# pic_k42.net
KiCad netlist of a schematic drawn in EAGLE
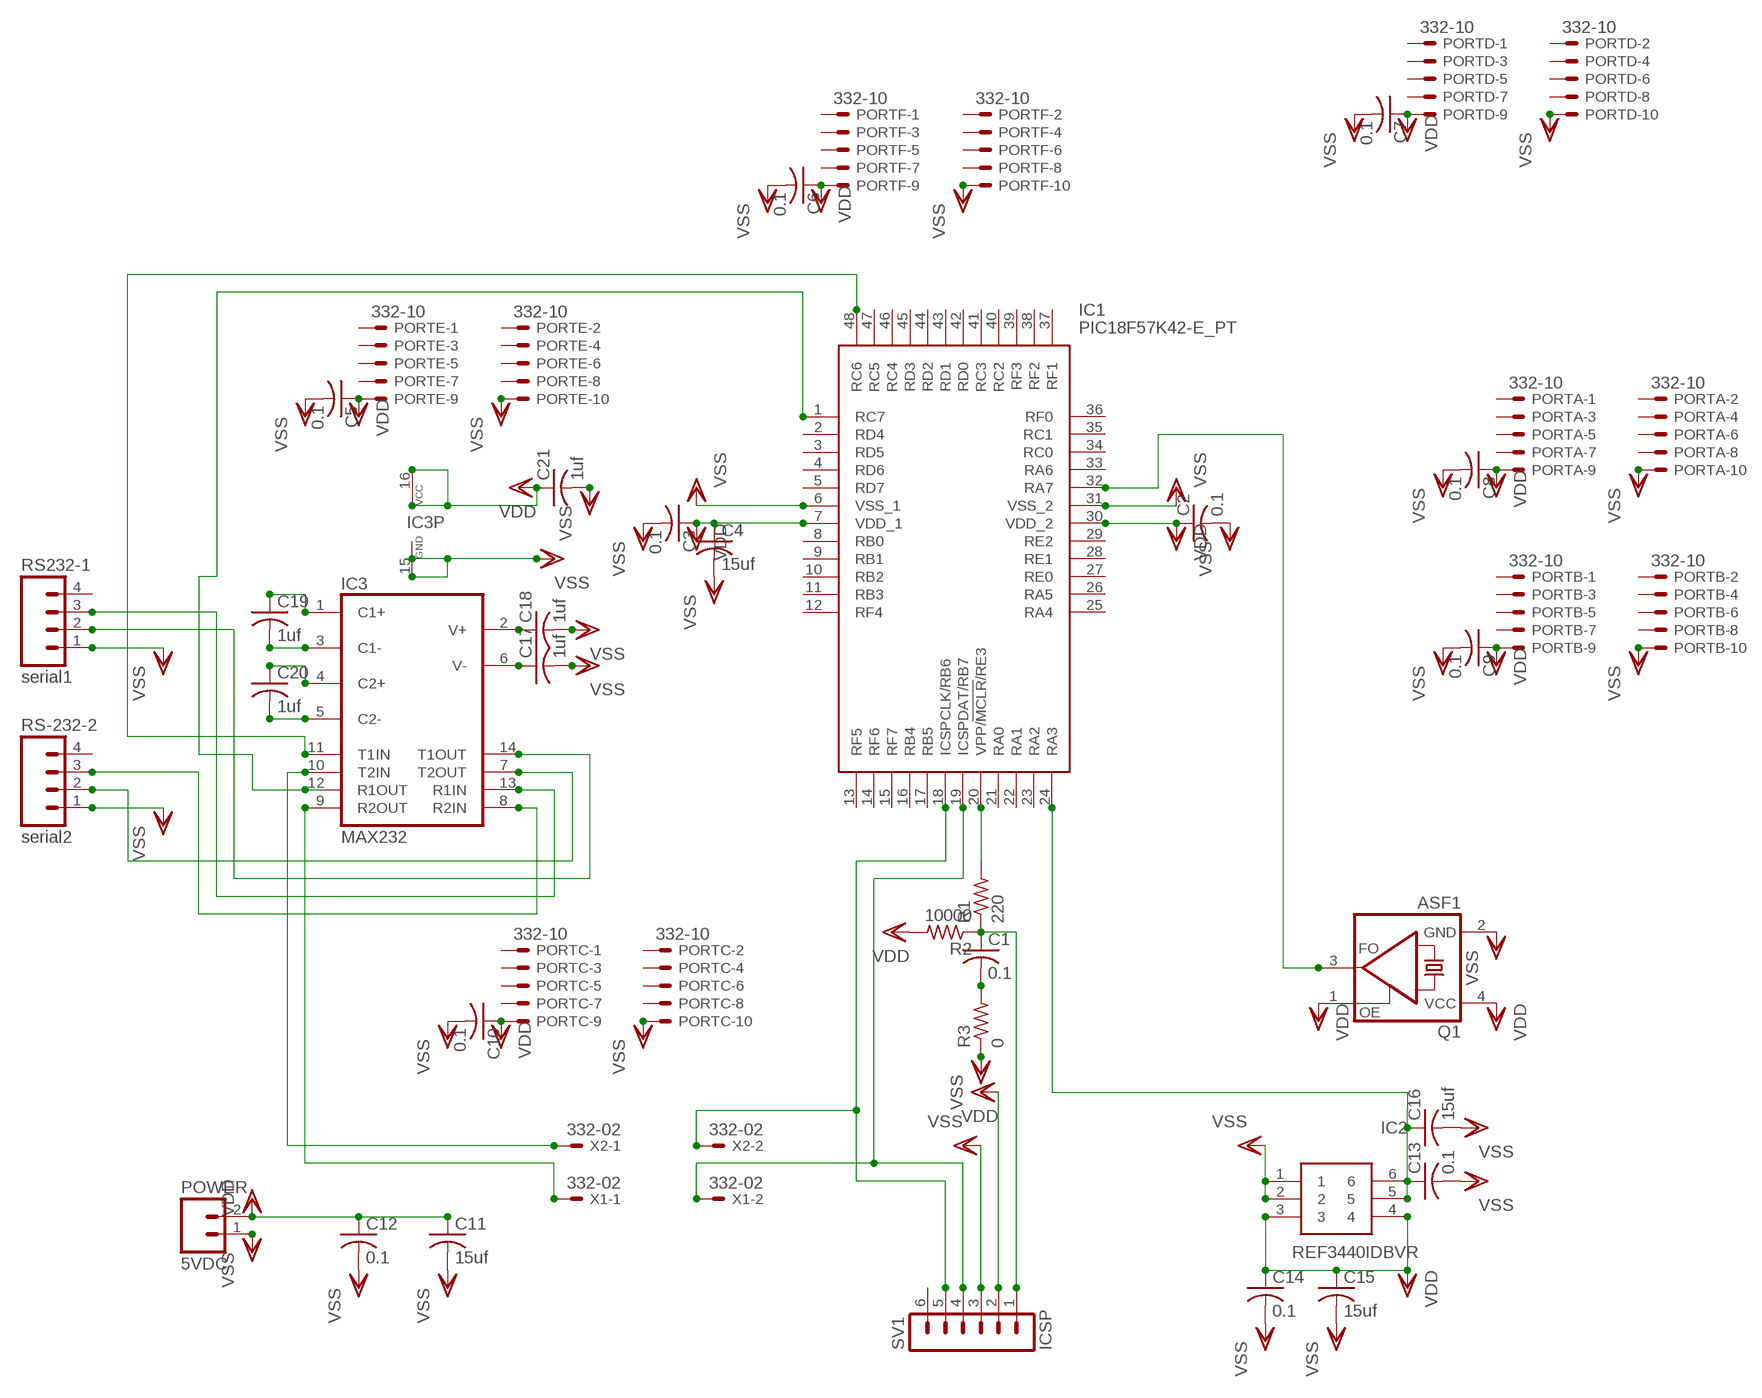
[diagram p0: schematic, sheet 1]

(export (version "E")
  (design (tool "Eeschema 10.0.6"))
  (components
    (comp (ref "C1")
      (value "0.1")
      (footprint "eagle-import:C1206")
      (libsource (lib "eagle-import") (part "C-USC1206"))
    )
    (comp (ref "C2")
      (value "0.1")
      (footprint "eagle-import:C1206")
      (libsource (lib "eagle-import") (part "C-USC1206"))
    )
    (comp (ref "C3")
      (value "0.1")
      (footprint "eagle-import:C1206")
      (libsource (lib "eagle-import") (part "C-USC1206"))
    )
    (comp (ref "C4")
      (value "15uf")
      (footprint "eagle-import:C1206")
      (libsource (lib "eagle-import") (part "C-USC1206"))
    )
    (comp (ref "C5")
      (value "0.1")
      (footprint "eagle-import:C1206")
      (libsource (lib "eagle-import") (part "C-USC1206"))
    )
    (comp (ref "C6")
      (value "0.1")
      (footprint "eagle-import:C1206")
      (libsource (lib "eagle-import") (part "C-USC1206"))
    )
    (comp (ref "C7")
      (value "0.1")
      (footprint "eagle-import:C1206")
      (libsource (lib "eagle-import") (part "C-USC1206"))
    )
    (comp (ref "C8")
      (value "0.1")
      (footprint "eagle-import:C1206")
      (libsource (lib "eagle-import") (part "C-USC1206"))
    )
    (comp (ref "C9")
      (value "0.1")
      (footprint "eagle-import:C1206")
      (libsource (lib "eagle-import") (part "C-USC1206"))
    )
    (comp (ref "C10")
      (value "0.1")
      (footprint "eagle-import:C1206")
      (libsource (lib "eagle-import") (part "C-USC1206"))
    )
    (comp (ref "C11")
      (value "15uf")
      (footprint "eagle-import:C1206")
      (libsource (lib "eagle-import") (part "C-USC1206"))
    )
    (comp (ref "C12")
      (value "0.1")
      (footprint "eagle-import:C1206")
      (libsource (lib "eagle-import") (part "C-USC1206"))
    )
    (comp (ref "C13")
      (value "0.1")
      (footprint "eagle-import:C1206")
      (libsource (lib "eagle-import") (part "C-USC1206"))
    )
    (comp (ref "C14")
      (value "0.1")
      (footprint "eagle-import:C1206")
      (libsource (lib "eagle-import") (part "C-USC1206"))
    )
    (comp (ref "C15")
      (value "15uf")
      (footprint "eagle-import:C1206")
      (libsource (lib "eagle-import") (part "C-USC1206"))
    )
    (comp (ref "C16")
      (value "15uf")
      (footprint "eagle-import:C1206")
      (libsource (lib "eagle-import") (part "C-USC1206"))
    )
    (comp (ref "C17")
      (value "1uf")
      (footprint "eagle-import:C0805")
      (libsource (lib "eagle-import") (part "C-USC0805"))
    )
    (comp (ref "C18")
      (value "1uf")
      (footprint "eagle-import:C0805")
      (libsource (lib "eagle-import") (part "C-USC0805"))
    )
    (comp (ref "C19")
      (value "1uf")
      (footprint "eagle-import:C0805")
      (libsource (lib "eagle-import") (part "C-USC0805"))
    )
    (comp (ref "C20")
      (value "1uf")
      (footprint "eagle-import:C0805")
      (libsource (lib "eagle-import") (part "C-USC0805"))
    )
    (comp (ref "C21")
      (value "1uf")
      (footprint "eagle-import:C0805")
      (libsource (lib "eagle-import") (part "C-USC0805"))
    )
    (comp (ref "IC1")
      (value "PIC18F57K42-E_PT")
      (footprint "eagle-import:QFP50P900X900X120-48N")
      (fields
        (field (name "MANUFACTURER_PART_NUMBER") "PIC18F57K42-E/PT")
        (field (name "MOUSER_PART_NUMBER") "579-PIC18F57K42-E/PT")
      )
      (libsource (lib "eagle-import") (part "PIC18F57K42-E_PT"))
    )
    (comp (ref "IC2")
      (value "REF3440IDBVR")
      (footprint "eagle-import:SOP95P280X145-6N")
      (libsource (lib "eagle-import") (part "REF3440IDBVR"))
    )
    (comp (ref "IC3")
      (value "MAX232")
      (footprint "eagle-import:DIL16")
      (fields (field (name "MF") "MAXIM") (field (name "MPN") "MAX232ACPE+"))
      (libsource (lib "eagle-import") (part "MAX232"))
    )
    (comp (ref "PORTA")
      (value "332-10")
      (footprint "eagle-import:332-10")
      (libsource (lib "eagle-import") (part "332-10"))
    )
    (comp (ref "PORTB")
      (value "332-10")
      (footprint "eagle-import:332-10")
      (libsource (lib "eagle-import") (part "332-10"))
    )
    (comp (ref "PORTC")
      (value "332-10")
      (footprint "eagle-import:332-10")
      (libsource (lib "eagle-import") (part "332-10"))
    )
    (comp (ref "PORTD")
      (value "332-10")
      (footprint "eagle-import:332-10")
      (libsource (lib "eagle-import") (part "332-10"))
    )
    (comp (ref "PORTE")
      (value "332-10")
      (footprint "eagle-import:332-10")
      (libsource (lib "eagle-import") (part "332-10"))
    )
    (comp (ref "PORTF")
      (value "332-10")
      (footprint "eagle-import:332-10")
      (libsource (lib "eagle-import") (part "332-10"))
    )
    (comp (ref "POWER")
      (value "5VDC")
      (footprint "eagle-import:02P")
      (libsource (lib "eagle-import") (part "M02"))
    )
    (comp (ref "Q1")
      (value "ASF1")
      (footprint "eagle-import:ASF")
      (libsource (lib "eagle-import") (part "ASF1"))
    )
    (comp (ref "R1")
      (value "220")
      (footprint "eagle-import:R1206")
      (libsource (lib "eagle-import") (part "R-US_R1206"))
    )
    (comp (ref "R2")
      (value "10000")
      (footprint "eagle-import:R1206")
      (libsource (lib "eagle-import") (part "R-US_R1206"))
    )
    (comp (ref "R3")
      (value "0")
      (footprint "eagle-import:R1206")
      (libsource (lib "eagle-import") (part "R-US_R1206"))
    )
    (comp (ref "RS-232-2")
      (value "serial2")
      (footprint "eagle-import:04P")
      (libsource (lib "eagle-import") (part "M04"))
    )
    (comp (ref "RS232-1")
      (value "serial1")
      (footprint "eagle-import:04P")
      (libsource (lib "eagle-import") (part "M04"))
    )
    (comp (ref "SV1")
      (value "ICSP")
      (footprint "eagle-import:MA06-1")
      (libsource (lib "eagle-import") (part "MA06-1"))
    )
    (comp (ref "X1")
      (value "332-02")
      (footprint "eagle-import:332-02")
      (libsource (lib "eagle-import") (part "332-02"))
    )
    (comp (ref "X2")
      (value "332-02")
      (footprint "eagle-import:332-02")
      (libsource (lib "eagle-import") (part "332-02"))
    )
  )
  (nets
    (net (code "1") (name "Net-(C1-Pad1)") (class "Default")
      (node (ref "C1") (pin "1") (pinfunction "1_1") (pintype "passive"))
      (node (ref "R1") (pin "1") (pinfunction "1_1") (pintype "passive"))
      (node (ref "R2") (pin "1") (pinfunction "1_1") (pintype "passive"))
      (node (ref "SV1") (pin "1") (pinfunction "1_1") (pintype "passive"))
    )
    (net (code "2") (name "Net-(C1-Pad2)") (class "Default")
      (node (ref "C1") (pin "2") (pinfunction "2_2") (pintype "passive"))
      (node (ref "R3") (pin "2") (pinfunction "2_2") (pintype "passive"))
    )
    (net (code "3") (name "Net-(IC1-ICSPCLK{slash}RB6)") (class "Default")
      (node (ref "IC1") (pin "18") (pinfunction "ICSPCLK/RB6_18") (pintype "bidirectional"))
      (node (ref "SV1") (pin "5") (pinfunction "5_5") (pintype "passive"))
      (node (ref "X2") (pin "2") (pinfunction "S_2") (pintype "passive"))
    )
    (net (code "4") (name "Net-(IC1-ICSPDAT{slash}RB7)") (class "Default")
      (node (ref "IC1") (pin "19") (pinfunction "ICSPDAT/RB7_19") (pintype "bidirectional"))
      (node (ref "SV1") (pin "4") (pinfunction "4_4") (pintype "passive"))
      (node (ref "X1") (pin "2") (pinfunction "S_2") (pintype "passive"))
    )
    (net (code "5") (name "Net-(IC1-RA3)") (class "Default")
      (node (ref "C13") (pin "1") (pinfunction "1_1") (pintype "passive"))
      (node (ref "C16") (pin "1") (pinfunction "1_1") (pintype "passive"))
      (node (ref "IC1") (pin "24") (pinfunction "RA3_24") (pintype "bidirectional"))
      (node (ref "IC2") (pin "5") (pinfunction "5_5") (pintype "bidirectional"))
      (node (ref "IC2") (pin "6") (pinfunction "6_6") (pintype "bidirectional"))
    )
    (net (code "6") (name "Net-(IC1-RA7)") (class "Default")
      (node (ref "IC1") (pin "32") (pinfunction "RA7_32") (pintype "bidirectional"))
      (node (ref "Q1") (pin "3") (pinfunction "FO_3") (pintype "output"))
    )
    (net (code "7") (name "Net-(IC1-RC6)") (class "Default")
      (node (ref "IC1") (pin "48") (pinfunction "RC6_48") (pintype "bidirectional"))
      (node (ref "IC3") (pin "11") (pinfunction "T1IN_11") (pintype "input"))
    )
    (net (code "8") (name "Net-(IC1-RC7)") (class "Default")
      (node (ref "IC1") (pin "1") (pinfunction "RC7_1") (pintype "bidirectional"))
      (node (ref "IC3") (pin "12") (pinfunction "R1OUT_12") (pintype "output"))
    )
    (net (code "9") (name "Net-(IC1-VPP{slash}~{MCLR}{slash}RE3)") (class "Default")
      (node (ref "IC1") (pin "20") (pinfunction "VPP/~{MCLR}/RE3_20") (pintype "bidirectional"))
      (node (ref "R1") (pin "2") (pinfunction "2_2") (pintype "passive"))
    )
    (net (code "10") (name "Net-(IC3A-C1+)") (class "Default")
      (node (ref "C19") (pin "1") (pinfunction "1_1") (pintype "passive"))
      (node (ref "IC3") (pin "1") (pinfunction "C1+_1") (pintype "bidirectional"))
    )
    (net (code "11") (name "Net-(IC3A-C1-)") (class "Default")
      (node (ref "C19") (pin "2") (pinfunction "2_2") (pintype "passive"))
      (node (ref "IC3") (pin "3") (pinfunction "C1-_3") (pintype "bidirectional"))
    )
    (net (code "12") (name "Net-(IC3A-C2+)") (class "Default")
      (node (ref "C20") (pin "1") (pinfunction "1_1") (pintype "passive"))
      (node (ref "IC3") (pin "4") (pinfunction "C2+_4") (pintype "bidirectional"))
    )
    (net (code "13") (name "Net-(IC3A-C2-)") (class "Default")
      (node (ref "C20") (pin "2") (pinfunction "2_2") (pintype "passive"))
      (node (ref "IC3") (pin "5") (pinfunction "C2-_5") (pintype "bidirectional"))
    )
    (net (code "14") (name "Net-(IC3A-R1IN)") (class "Default")
      (node (ref "IC3") (pin "13") (pinfunction "R1IN_13") (pintype "input"))
      (node (ref "RS232-1") (pin "3") (pinfunction "3_3") (pintype "passive"))
    )
    (net (code "15") (name "Net-(IC3A-R2IN)") (class "Default")
      (node (ref "IC3") (pin "8") (pinfunction "R2IN_8") (pintype "input"))
      (node (ref "RS-232-2") (pin "3") (pinfunction "3_3") (pintype "passive"))
    )
    (net (code "16") (name "Net-(IC3A-R2OUT)") (class "Default")
      (node (ref "IC3") (pin "9") (pinfunction "R2OUT_9") (pintype "output"))
      (node (ref "X1") (pin "1") (pinfunction "S_1") (pintype "passive"))
    )
    (net (code "17") (name "Net-(IC3A-T1OUT)") (class "Default")
      (node (ref "IC3") (pin "14") (pinfunction "T1OUT_14") (pintype "output"))
      (node (ref "RS232-1") (pin "2") (pinfunction "2_2") (pintype "passive"))
    )
    (net (code "18") (name "Net-(IC3A-T2IN)") (class "Default")
      (node (ref "IC3") (pin "10") (pinfunction "T2IN_10") (pintype "input"))
      (node (ref "X2") (pin "1") (pinfunction "S_1") (pintype "passive"))
    )
    (net (code "19") (name "Net-(IC3A-T2OUT)") (class "Default")
      (node (ref "IC3") (pin "7") (pinfunction "T2OUT_7") (pintype "output"))
      (node (ref "RS-232-2") (pin "2") (pinfunction "2_2") (pintype "passive"))
    )
    (net (code "20") (name "Net-(IC3A-V+)") (class "Default")
      (node (ref "C18") (pin "1") (pinfunction "1_1") (pintype "passive"))
      (node (ref "IC3") (pin "2") (pinfunction "V+_2") (pintype "bidirectional"))
    )
    (net (code "21") (name "Net-(IC3A-V-)") (class "Default")
      (node (ref "C17") (pin "1") (pinfunction "1_1") (pintype "passive"))
      (node (ref "IC3") (pin "6") (pinfunction "V-_6") (pintype "bidirectional"))
    )
    (net (code "22") (name "VDD") (class "Default")
      (node (ref "C10") (pin "1") (pinfunction "1_1") (pintype "passive"))
      (node (ref "C11") (pin "1") (pinfunction "1_1") (pintype "passive"))
      (node (ref "C12") (pin "1") (pinfunction "1_1") (pintype "passive"))
      (node (ref "C14") (pin "1") (pinfunction "1_1") (pintype "passive"))
      (node (ref "C15") (pin "1") (pinfunction "1_1") (pintype "passive"))
      (node (ref "C2") (pin "1") (pinfunction "1_1") (pintype "passive"))
      (node (ref "C21") (pin "1") (pinfunction "1_1") (pintype "passive"))
      (node (ref "C3") (pin "1") (pinfunction "1_1") (pintype "passive"))
      (node (ref "C4") (pin "1") (pinfunction "1_1") (pintype "passive"))
      (node (ref "C5") (pin "1") (pinfunction "1_1") (pintype "passive"))
      (node (ref "C6") (pin "1") (pinfunction "1_1") (pintype "passive"))
      (node (ref "C7") (pin "1") (pinfunction "1_1") (pintype "passive"))
      (node (ref "C8") (pin "1") (pinfunction "1_1") (pintype "passive"))
      (node (ref "C9") (pin "1") (pinfunction "1_1") (pintype "passive"))
      (node (ref "IC1") (pin "30") (pinfunction "VDD_2_30") (pintype "bidirectional"))
      (node (ref "IC1") (pin "7") (pinfunction "VDD_1_7") (pintype "bidirectional"))
      (node (ref "IC2") (pin "3") (pinfunction "3_3") (pintype "bidirectional"))
      (node (ref "IC2") (pin "4") (pinfunction "4_4") (pintype "bidirectional"))
      (node (ref "IC3") (pin "16") (pinfunction "VCC_16") (pintype "power_in"))
      (node (ref "PORTA") (pin "9") (pinfunction "S_9") (pintype "passive"))
      (node (ref "PORTB") (pin "9") (pinfunction "S_9") (pintype "passive"))
      (node (ref "PORTC") (pin "9") (pinfunction "S_9") (pintype "passive"))
      (node (ref "PORTD") (pin "9") (pinfunction "S_9") (pintype "passive"))
      (node (ref "PORTE") (pin "9") (pinfunction "S_9") (pintype "passive"))
      (node (ref "PORTF") (pin "9") (pinfunction "S_9") (pintype "passive"))
      (node (ref "POWER") (pin "2") (pinfunction "2_2") (pintype "passive"))
      (node (ref "Q1") (pin "1") (pinfunction "OE_1") (pintype "input"))
      (node (ref "Q1") (pin "4") (pinfunction "VCC_4") (pintype "power_in"))
      (node (ref "R2") (pin "2") (pinfunction "2_2") (pintype "passive"))
      (node (ref "SV1") (pin "2") (pinfunction "2_2") (pintype "passive"))
    )
    (net (code "23") (name "VSS") (class "Default")
      (node (ref "C10") (pin "2") (pinfunction "2_2") (pintype "passive"))
      (node (ref "C11") (pin "2") (pinfunction "2_2") (pintype "passive"))
      (node (ref "C12") (pin "2") (pinfunction "2_2") (pintype "passive"))
      (node (ref "C13") (pin "2") (pinfunction "2_2") (pintype "passive"))
      (node (ref "C14") (pin "2") (pinfunction "2_2") (pintype "passive"))
      (node (ref "C15") (pin "2") (pinfunction "2_2") (pintype "passive"))
      (node (ref "C16") (pin "2") (pinfunction "2_2") (pintype "passive"))
      (node (ref "C17") (pin "2") (pinfunction "2_2") (pintype "passive"))
      (node (ref "C18") (pin "2") (pinfunction "2_2") (pintype "passive"))
      (node (ref "C2") (pin "2") (pinfunction "2_2") (pintype "passive"))
      (node (ref "C21") (pin "2") (pinfunction "2_2") (pintype "passive"))
      (node (ref "C3") (pin "2") (pinfunction "2_2") (pintype "passive"))
      (node (ref "C4") (pin "2") (pinfunction "2_2") (pintype "passive"))
      (node (ref "C5") (pin "2") (pinfunction "2_2") (pintype "passive"))
      (node (ref "C6") (pin "2") (pinfunction "2_2") (pintype "passive"))
      (node (ref "C7") (pin "2") (pinfunction "2_2") (pintype "passive"))
      (node (ref "C8") (pin "2") (pinfunction "2_2") (pintype "passive"))
      (node (ref "C9") (pin "2") (pinfunction "2_2") (pintype "passive"))
      (node (ref "IC1") (pin "31") (pinfunction "VSS_2_31") (pintype "bidirectional"))
      (node (ref "IC1") (pin "6") (pinfunction "VSS_1_6") (pintype "bidirectional"))
      (node (ref "IC2") (pin "1") (pinfunction "1_1") (pintype "bidirectional"))
      (node (ref "IC2") (pin "2") (pinfunction "2_2") (pintype "bidirectional"))
      (node (ref "IC3") (pin "15") (pinfunction "GND_15") (pintype "power_in"))
      (node (ref "PORTA") (pin "10") (pinfunction "S_10") (pintype "passive"))
      (node (ref "PORTB") (pin "10") (pinfunction "S_10") (pintype "passive"))
      (node (ref "PORTC") (pin "10") (pinfunction "S_10") (pintype "passive"))
      (node (ref "PORTD") (pin "10") (pinfunction "S_10") (pintype "passive"))
      (node (ref "PORTE") (pin "10") (pinfunction "S_10") (pintype "passive"))
      (node (ref "PORTF") (pin "10") (pinfunction "S_10") (pintype "passive"))
      (node (ref "POWER") (pin "1") (pinfunction "1_1") (pintype "passive"))
      (node (ref "Q1") (pin "2") (pinfunction "GND_2") (pintype "power_in"))
      (node (ref "R3") (pin "1") (pinfunction "1_1") (pintype "passive"))
      (node (ref "RS-232-2") (pin "1") (pinfunction "1_1") (pintype "passive"))
      (node (ref "RS232-1") (pin "1") (pinfunction "1_1") (pintype "passive"))
      (node (ref "SV1") (pin "3") (pinfunction "3_3") (pintype "passive"))
    )
    (net (code "24") (name "unconnected-(IC1-RA0-Pad21)") (class "Default")
      (node (ref "IC1") (pin "21") (pinfunction "RA0_21") (pintype "bidirectional"))
    )
    (net (code "25") (name "unconnected-(IC1-RA1-Pad22)") (class "Default")
      (node (ref "IC1") (pin "22") (pinfunction "RA1_22") (pintype "bidirectional"))
    )
    (net (code "26") (name "unconnected-(IC1-RA2-Pad23)") (class "Default")
      (node (ref "IC1") (pin "23") (pinfunction "RA2_23") (pintype "bidirectional"))
    )
    (net (code "27") (name "unconnected-(IC1-RA4-Pad25)") (class "Default")
      (node (ref "IC1") (pin "25") (pinfunction "RA4_25") (pintype "bidirectional"))
    )
    (net (code "28") (name "unconnected-(IC1-RA5-Pad26)") (class "Default")
      (node (ref "IC1") (pin "26") (pinfunction "RA5_26") (pintype "bidirectional"))
    )
    (net (code "29") (name "unconnected-(IC1-RA6-Pad33)") (class "Default")
      (node (ref "IC1") (pin "33") (pinfunction "RA6_33") (pintype "bidirectional"))
    )
    (net (code "30") (name "unconnected-(IC1-RB0-Pad8)") (class "Default")
      (node (ref "IC1") (pin "8") (pinfunction "RB0_8") (pintype "bidirectional"))
    )
    (net (code "31") (name "unconnected-(IC1-RB1-Pad9)") (class "Default")
      (node (ref "IC1") (pin "9") (pinfunction "RB1_9") (pintype "bidirectional"))
    )
    (net (code "32") (name "unconnected-(IC1-RB2-Pad10)") (class "Default")
      (node (ref "IC1") (pin "10") (pinfunction "RB2_10") (pintype "bidirectional"))
    )
    (net (code "33") (name "unconnected-(IC1-RB3-Pad11)") (class "Default")
      (node (ref "IC1") (pin "11") (pinfunction "RB3_11") (pintype "bidirectional"))
    )
    (net (code "34") (name "unconnected-(IC1-RB4-Pad16)") (class "Default")
      (node (ref "IC1") (pin "16") (pinfunction "RB4_16") (pintype "bidirectional"))
    )
    (net (code "35") (name "unconnected-(IC1-RB5-Pad17)") (class "Default")
      (node (ref "IC1") (pin "17") (pinfunction "RB5_17") (pintype "bidirectional"))
    )
    (net (code "36") (name "unconnected-(IC1-RC0-Pad34)") (class "Default")
      (node (ref "IC1") (pin "34") (pinfunction "RC0_34") (pintype "bidirectional"))
    )
    (net (code "37") (name "unconnected-(IC1-RC1-Pad35)") (class "Default")
      (node (ref "IC1") (pin "35") (pinfunction "RC1_35") (pintype "bidirectional"))
    )
    (net (code "38") (name "unconnected-(IC1-RC2-Pad40)") (class "Default")
      (node (ref "IC1") (pin "40") (pinfunction "RC2_40") (pintype "bidirectional"))
    )
    (net (code "39") (name "unconnected-(IC1-RC3-Pad41)") (class "Default")
      (node (ref "IC1") (pin "41") (pinfunction "RC3_41") (pintype "bidirectional"))
    )
    (net (code "40") (name "unconnected-(IC1-RC4-Pad46)") (class "Default")
      (node (ref "IC1") (pin "46") (pinfunction "RC4_46") (pintype "bidirectional"))
    )
    (net (code "41") (name "unconnected-(IC1-RC5-Pad47)") (class "Default")
      (node (ref "IC1") (pin "47") (pinfunction "RC5_47") (pintype "bidirectional"))
    )
    (net (code "42") (name "unconnected-(IC1-RD0-Pad42)") (class "Default")
      (node (ref "IC1") (pin "42") (pinfunction "RD0_42") (pintype "bidirectional"))
    )
    (net (code "43") (name "unconnected-(IC1-RD1-Pad43)") (class "Default")
      (node (ref "IC1") (pin "43") (pinfunction "RD1_43") (pintype "bidirectional"))
    )
    (net (code "44") (name "unconnected-(IC1-RD2-Pad44)") (class "Default")
      (node (ref "IC1") (pin "44") (pinfunction "RD2_44") (pintype "bidirectional"))
    )
    (net (code "45") (name "unconnected-(IC1-RD3-Pad45)") (class "Default")
      (node (ref "IC1") (pin "45") (pinfunction "RD3_45") (pintype "bidirectional"))
    )
    (net (code "46") (name "unconnected-(IC1-RD4-Pad2)") (class "Default")
      (node (ref "IC1") (pin "2") (pinfunction "RD4_2") (pintype "bidirectional"))
    )
    (net (code "47") (name "unconnected-(IC1-RD5-Pad3)") (class "Default")
      (node (ref "IC1") (pin "3") (pinfunction "RD5_3") (pintype "bidirectional"))
    )
    (net (code "48") (name "unconnected-(IC1-RD6-Pad4)") (class "Default")
      (node (ref "IC1") (pin "4") (pinfunction "RD6_4") (pintype "bidirectional"))
    )
    (net (code "49") (name "unconnected-(IC1-RD7-Pad5)") (class "Default")
      (node (ref "IC1") (pin "5") (pinfunction "RD7_5") (pintype "bidirectional"))
    )
    (net (code "50") (name "unconnected-(IC1-RE0-Pad27)") (class "Default")
      (node (ref "IC1") (pin "27") (pinfunction "RE0_27") (pintype "bidirectional"))
    )
    (net (code "51") (name "unconnected-(IC1-RE1-Pad28)") (class "Default")
      (node (ref "IC1") (pin "28") (pinfunction "RE1_28") (pintype "bidirectional"))
    )
    (net (code "52") (name "unconnected-(IC1-RE2-Pad29)") (class "Default")
      (node (ref "IC1") (pin "29") (pinfunction "RE2_29") (pintype "bidirectional"))
    )
    (net (code "53") (name "unconnected-(IC1-RF0-Pad36)") (class "Default")
      (node (ref "IC1") (pin "36") (pinfunction "RF0_36") (pintype "bidirectional"))
    )
    (net (code "54") (name "unconnected-(IC1-RF1-Pad37)") (class "Default")
      (node (ref "IC1") (pin "37") (pinfunction "RF1_37") (pintype "bidirectional"))
    )
    (net (code "55") (name "unconnected-(IC1-RF2-Pad38)") (class "Default")
      (node (ref "IC1") (pin "38") (pinfunction "RF2_38") (pintype "bidirectional"))
    )
    (net (code "56") (name "unconnected-(IC1-RF3-Pad39)") (class "Default")
      (node (ref "IC1") (pin "39") (pinfunction "RF3_39") (pintype "bidirectional"))
    )
    (net (code "57") (name "unconnected-(IC1-RF4-Pad12)") (class "Default")
      (node (ref "IC1") (pin "12") (pinfunction "RF4_12") (pintype "bidirectional"))
    )
    (net (code "58") (name "unconnected-(IC1-RF5-Pad13)") (class "Default")
      (node (ref "IC1") (pin "13") (pinfunction "RF5_13") (pintype "bidirectional"))
    )
    (net (code "59") (name "unconnected-(IC1-RF6-Pad14)") (class "Default")
      (node (ref "IC1") (pin "14") (pinfunction "RF6_14") (pintype "bidirectional"))
    )
    (net (code "60") (name "unconnected-(IC1-RF7-Pad15)") (class "Default")
      (node (ref "IC1") (pin "15") (pinfunction "RF7_15") (pintype "bidirectional"))
    )
    (net (code "61") (name "unconnected-(PORTAA-S-Pad1)") (class "Default")
      (node (ref "PORTA") (pin "1") (pinfunction "S_1") (pintype "passive"))
    )
    (net (code "62") (name "unconnected-(PORTAC-S-Pad2)") (class "Default")
      (node (ref "PORTA") (pin "2") (pinfunction "S_2") (pintype "passive"))
    )
    (net (code "63") (name "unconnected-(PORTAD-S-Pad3)") (class "Default")
      (node (ref "PORTA") (pin "3") (pinfunction "S_3") (pintype "passive"))
    )
    (net (code "64") (name "unconnected-(PORTAE-S-Pad4)") (class "Default")
      (node (ref "PORTA") (pin "4") (pinfunction "S_4") (pintype "passive"))
    )
    (net (code "65") (name "unconnected-(PORTAF-S-Pad5)") (class "Default")
      (node (ref "PORTA") (pin "5") (pinfunction "S_5") (pintype "passive"))
    )
    (net (code "66") (name "unconnected-(PORTAG-S-Pad6)") (class "Default")
      (node (ref "PORTA") (pin "6") (pinfunction "S_6") (pintype "passive"))
    )
    (net (code "67") (name "unconnected-(PORTAH-S-Pad7)") (class "Default")
      (node (ref "PORTA") (pin "7") (pinfunction "S_7") (pintype "passive"))
    )
    (net (code "68") (name "unconnected-(PORTAI-S-Pad8)") (class "Default")
      (node (ref "PORTA") (pin "8") (pinfunction "S_8") (pintype "passive"))
    )
    (net (code "69") (name "unconnected-(PORTBA-S-Pad1)") (class "Default")
      (node (ref "PORTB") (pin "1") (pinfunction "S_1") (pintype "passive"))
    )
    (net (code "70") (name "unconnected-(PORTBC-S-Pad2)") (class "Default")
      (node (ref "PORTB") (pin "2") (pinfunction "S_2") (pintype "passive"))
    )
    (net (code "71") (name "unconnected-(PORTBD-S-Pad3)") (class "Default")
      (node (ref "PORTB") (pin "3") (pinfunction "S_3") (pintype "passive"))
    )
    (net (code "72") (name "unconnected-(PORTBE-S-Pad4)") (class "Default")
      (node (ref "PORTB") (pin "4") (pinfunction "S_4") (pintype "passive"))
    )
    (net (code "73") (name "unconnected-(PORTBF-S-Pad5)") (class "Default")
      (node (ref "PORTB") (pin "5") (pinfunction "S_5") (pintype "passive"))
    )
    (net (code "74") (name "unconnected-(PORTBG-S-Pad6)") (class "Default")
      (node (ref "PORTB") (pin "6") (pinfunction "S_6") (pintype "passive"))
    )
    (net (code "75") (name "unconnected-(PORTBH-S-Pad7)") (class "Default")
      (node (ref "PORTB") (pin "7") (pinfunction "S_7") (pintype "passive"))
    )
    (net (code "76") (name "unconnected-(PORTBI-S-Pad8)") (class "Default")
      (node (ref "PORTB") (pin "8") (pinfunction "S_8") (pintype "passive"))
    )
    (net (code "77") (name "unconnected-(PORTCA-S-Pad1)") (class "Default")
      (node (ref "PORTC") (pin "1") (pinfunction "S_1") (pintype "passive"))
    )
    (net (code "78") (name "unconnected-(PORTCC-S-Pad2)") (class "Default")
      (node (ref "PORTC") (pin "2") (pinfunction "S_2") (pintype "passive"))
    )
    (net (code "79") (name "unconnected-(PORTCD-S-Pad3)") (class "Default")
      (node (ref "PORTC") (pin "3") (pinfunction "S_3") (pintype "passive"))
    )
    (net (code "80") (name "unconnected-(PORTCE-S-Pad4)") (class "Default")
      (node (ref "PORTC") (pin "4") (pinfunction "S_4") (pintype "passive"))
    )
    (net (code "81") (name "unconnected-(PORTCF-S-Pad5)") (class "Default")
      (node (ref "PORTC") (pin "5") (pinfunction "S_5") (pintype "passive"))
    )
    (net (code "82") (name "unconnected-(PORTCG-S-Pad6)") (class "Default")
      (node (ref "PORTC") (pin "6") (pinfunction "S_6") (pintype "passive"))
    )
    (net (code "83") (name "unconnected-(PORTCH-S-Pad7)") (class "Default")
      (node (ref "PORTC") (pin "7") (pinfunction "S_7") (pintype "passive"))
    )
    (net (code "84") (name "unconnected-(PORTCI-S-Pad8)") (class "Default")
      (node (ref "PORTC") (pin "8") (pinfunction "S_8") (pintype "passive"))
    )
    (net (code "85") (name "unconnected-(PORTDA-S-Pad1)") (class "Default")
      (node (ref "PORTD") (pin "1") (pinfunction "S_1") (pintype "passive"))
    )
    (net (code "86") (name "unconnected-(PORTDC-S-Pad2)") (class "Default")
      (node (ref "PORTD") (pin "2") (pinfunction "S_2") (pintype "passive"))
    )
    (net (code "87") (name "unconnected-(PORTDD-S-Pad3)") (class "Default")
      (node (ref "PORTD") (pin "3") (pinfunction "S_3") (pintype "passive"))
    )
    (net (code "88") (name "unconnected-(PORTDE-S-Pad4)") (class "Default")
      (node (ref "PORTD") (pin "4") (pinfunction "S_4") (pintype "passive"))
    )
    (net (code "89") (name "unconnected-(PORTDF-S-Pad5)") (class "Default")
      (node (ref "PORTD") (pin "5") (pinfunction "S_5") (pintype "passive"))
    )
    (net (code "90") (name "unconnected-(PORTDG-S-Pad6)") (class "Default")
      (node (ref "PORTD") (pin "6") (pinfunction "S_6") (pintype "passive"))
    )
    (net (code "91") (name "unconnected-(PORTDH-S-Pad7)") (class "Default")
      (node (ref "PORTD") (pin "7") (pinfunction "S_7") (pintype "passive"))
    )
    (net (code "92") (name "unconnected-(PORTDI-S-Pad8)") (class "Default")
      (node (ref "PORTD") (pin "8") (pinfunction "S_8") (pintype "passive"))
    )
    (net (code "93") (name "unconnected-(PORTEA-S-Pad1)") (class "Default")
      (node (ref "PORTE") (pin "1") (pinfunction "S_1") (pintype "passive"))
    )
    (net (code "94") (name "unconnected-(PORTEC-S-Pad2)") (class "Default")
      (node (ref "PORTE") (pin "2") (pinfunction "S_2") (pintype "passive"))
    )
    (net (code "95") (name "unconnected-(PORTED-S-Pad3)") (class "Default")
      (node (ref "PORTE") (pin "3") (pinfunction "S_3") (pintype "passive"))
    )
    (net (code "96") (name "unconnected-(PORTEE-S-Pad4)") (class "Default")
      (node (ref "PORTE") (pin "4") (pinfunction "S_4") (pintype "passive"))
    )
    (net (code "97") (name "unconnected-(PORTEF-S-Pad5)") (class "Default")
      (node (ref "PORTE") (pin "5") (pinfunction "S_5") (pintype "passive"))
    )
    (net (code "98") (name "unconnected-(PORTEG-S-Pad6)") (class "Default")
      (node (ref "PORTE") (pin "6") (pinfunction "S_6") (pintype "passive"))
    )
    (net (code "99") (name "unconnected-(PORTEH-S-Pad7)") (class "Default")
      (node (ref "PORTE") (pin "7") (pinfunction "S_7") (pintype "passive"))
    )
    (net (code "100") (name "unconnected-(PORTEI-S-Pad8)") (class "Default")
      (node (ref "PORTE") (pin "8") (pinfunction "S_8") (pintype "passive"))
    )
    (net (code "101") (name "unconnected-(PORTFA-S-Pad1)") (class "Default")
      (node (ref "PORTF") (pin "1") (pinfunction "S_1") (pintype "passive"))
    )
    (net (code "102") (name "unconnected-(PORTFC-S-Pad2)") (class "Default")
      (node (ref "PORTF") (pin "2") (pinfunction "S_2") (pintype "passive"))
    )
    (net (code "103") (name "unconnected-(PORTFD-S-Pad3)") (class "Default")
      (node (ref "PORTF") (pin "3") (pinfunction "S_3") (pintype "passive"))
    )
    (net (code "104") (name "unconnected-(PORTFE-S-Pad4)") (class "Default")
      (node (ref "PORTF") (pin "4") (pinfunction "S_4") (pintype "passive"))
    )
    (net (code "105") (name "unconnected-(PORTFF-S-Pad5)") (class "Default")
      (node (ref "PORTF") (pin "5") (pinfunction "S_5") (pintype "passive"))
    )
    (net (code "106") (name "unconnected-(PORTFG-S-Pad6)") (class "Default")
      (node (ref "PORTF") (pin "6") (pinfunction "S_6") (pintype "passive"))
    )
    (net (code "107") (name "unconnected-(PORTFH-S-Pad7)") (class "Default")
      (node (ref "PORTF") (pin "7") (pinfunction "S_7") (pintype "passive"))
    )
    (net (code "108") (name "unconnected-(PORTFI-S-Pad8)") (class "Default")
      (node (ref "PORTF") (pin "8") (pinfunction "S_8") (pintype "passive"))
    )
    (net (code "109") (name "unconnected-(RS-232-2-Pad4)") (class "Default")
      (node (ref "RS-232-2") (pin "4") (pinfunction "4_4") (pintype "passive"))
    )
    (net (code "110") (name "unconnected-(RS232-1-Pad4)") (class "Default")
      (node (ref "RS232-1") (pin "4") (pinfunction "4_4") (pintype "passive"))
    )
    (net (code "111") (name "unconnected-(SV1-Pad6)") (class "Default")
      (node (ref "SV1") (pin "6") (pinfunction "6_6") (pintype "passive"))
    )
  )
)
